# G826K.net
KiCad netlist of a schematic drawn in EAGLE
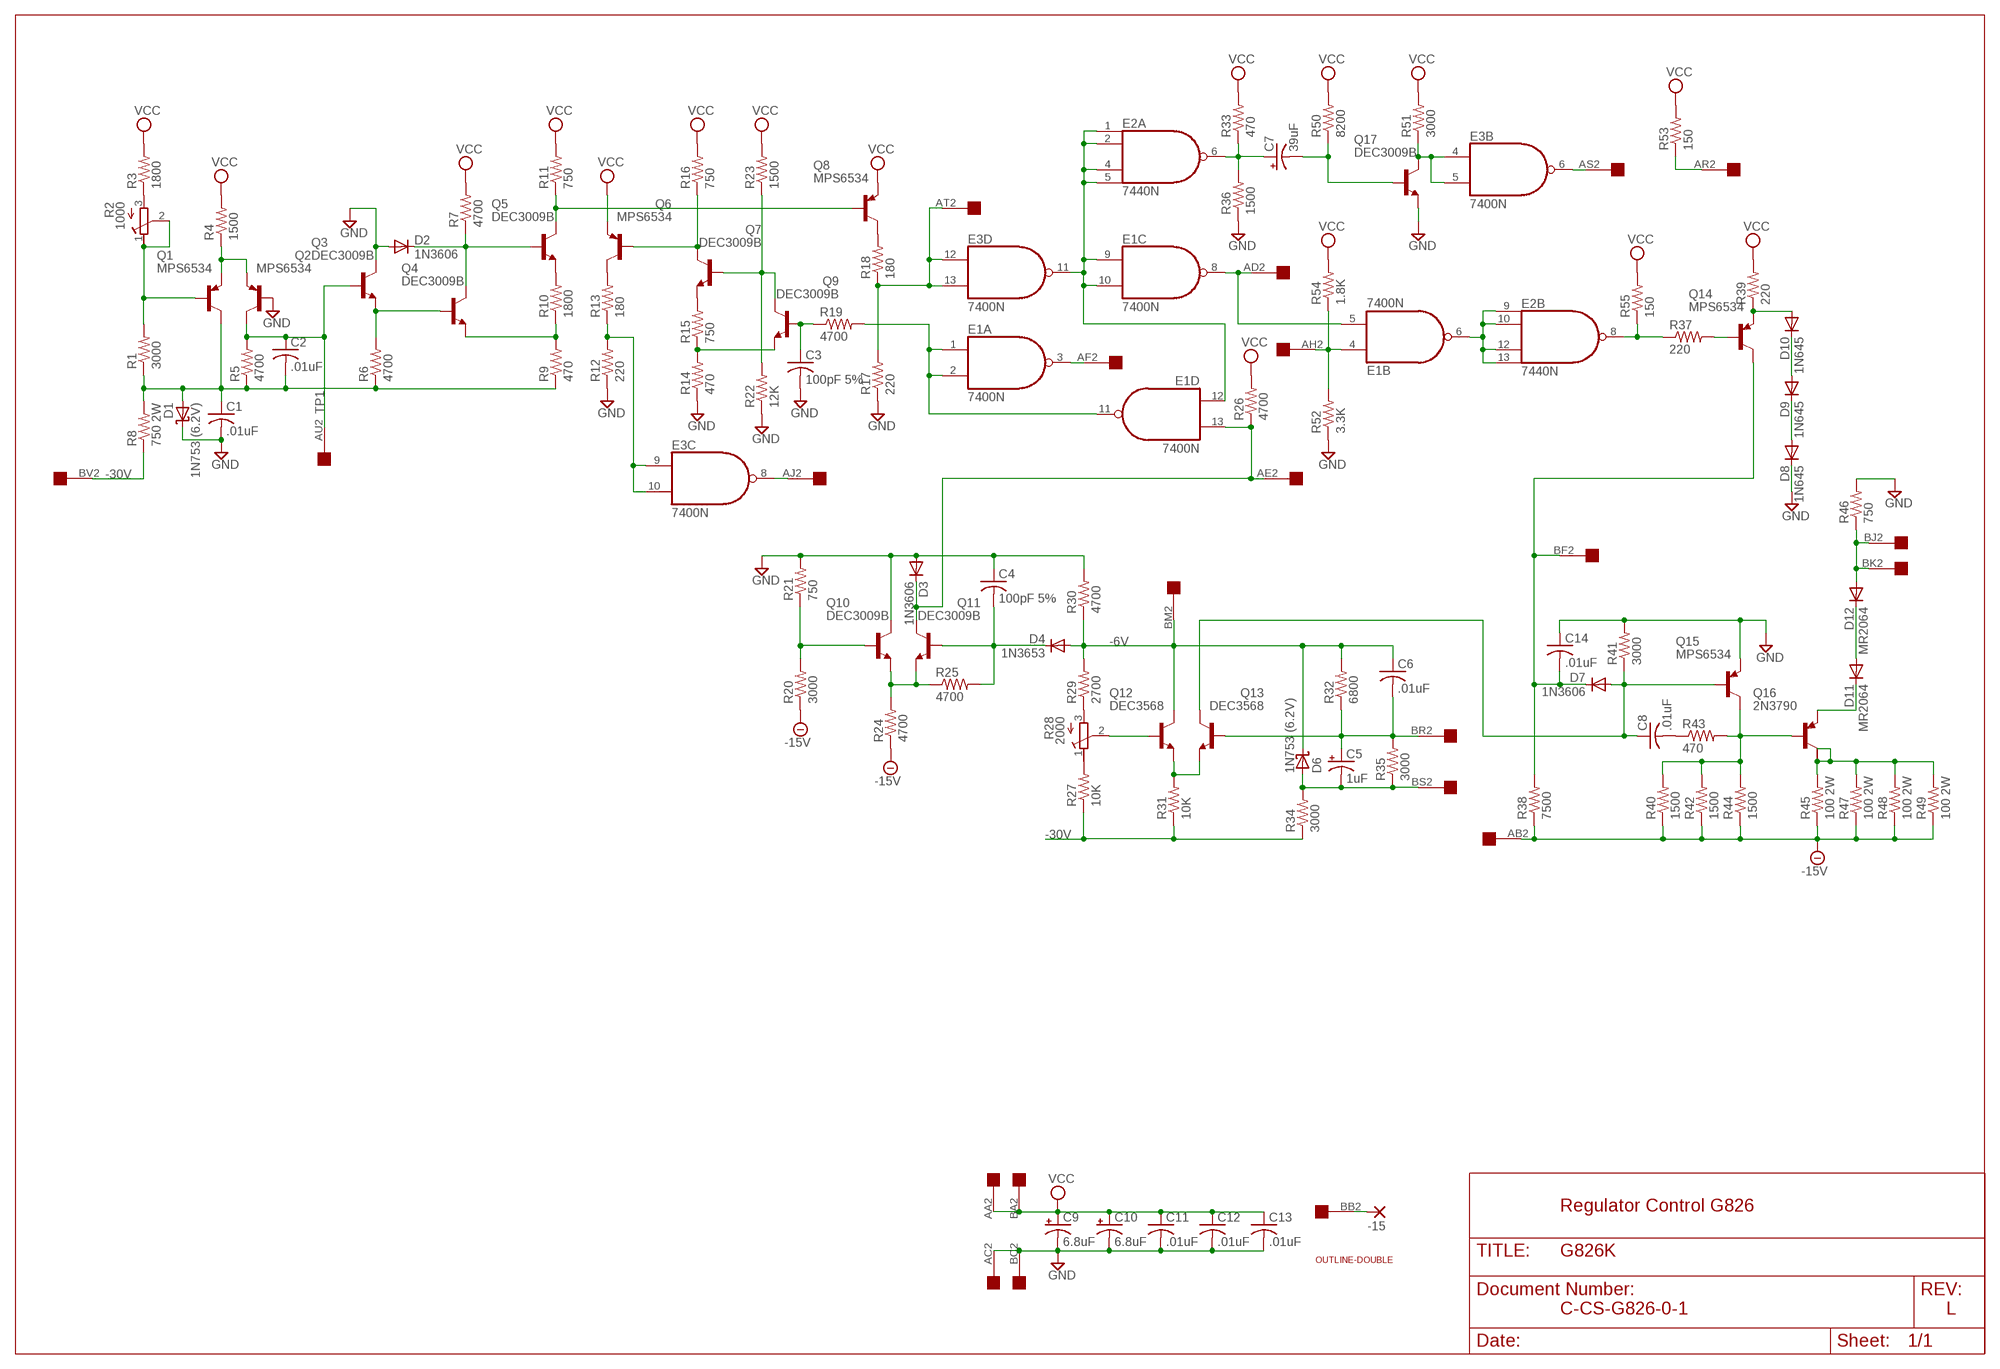
[diagram p0: schematic, sheet 1]

(export (version "E")
  (design (tool "Eeschema 10.0.6"))
  (components
    (comp (ref "-15")
      (value "1,6/0,8")
      (footprint "eagle-import:1,6_0,8")
      (libsource (lib "eagle-import") (part "1,6/0,8"))
    )
    (comp (ref "C1")
      (value ".01uF")
      (footprint "eagle-import:C050-025X075")
      (libsource (lib "eagle-import") (part "C-US050-025X075"))
    )
    (comp (ref "C2")
      (value ".01uF")
      (footprint "eagle-import:C050-025X075")
      (libsource (lib "eagle-import") (part "C-US050-025X075"))
    )
    (comp (ref "C3")
      (value "100pF 5%")
      (footprint "eagle-import:C050-025X075")
      (libsource (lib "eagle-import") (part "C-US050-025X075"))
    )
    (comp (ref "C4")
      (value "100pF 5%")
      (footprint "eagle-import:C050-025X075")
      (libsource (lib "eagle-import") (part "C-US050-025X075"))
    )
    (comp (ref "C5")
      (value "1uF")
      (footprint "eagle-import:E15-5")
      (libsource (lib "eagle-import") (part "CPOL-USE15-5AXIAL"))
    )
    (comp (ref "C6")
      (value ".01uF")
      (footprint "eagle-import:C050-025X075")
      (libsource (lib "eagle-import") (part "C-US050-025X075"))
    )
    (comp (ref "C7")
      (value "39uF")
      (footprint "eagle-import:E22-6")
      (libsource (lib "eagle-import") (part "CPOL-USE22-6AXIAL"))
    )
    (comp (ref "C8")
      (value ".01uF")
      (footprint "eagle-import:C050-025X075")
      (libsource (lib "eagle-import") (part "C-US050-025X075"))
    )
    (comp (ref "C9")
      (value "6.8uF")
      (footprint "eagle-import:E12-8")
      (libsource (lib "eagle-import") (part "CPOL-USE20-8AXIAL"))
    )
    (comp (ref "C10")
      (value "6.8uF")
      (footprint "eagle-import:E12-8")
      (libsource (lib "eagle-import") (part "CPOL-USE20-8AXIAL"))
    )
    (comp (ref "C11")
      (value ".01uF")
      (footprint "eagle-import:C050-025X075")
      (libsource (lib "eagle-import") (part "C-US050-025X075"))
    )
    (comp (ref "C12")
      (value ".01uF")
      (footprint "eagle-import:C050-025X075")
      (libsource (lib "eagle-import") (part "C-US050-025X075"))
    )
    (comp (ref "C13")
      (value ".01uF")
      (footprint "eagle-import:C050-025X075")
      (libsource (lib "eagle-import") (part "C-US050-025X075"))
    )
    (comp (ref "C14")
      (value ".01uF")
      (footprint "eagle-import:C050-025X075")
      (libsource (lib "eagle-import") (part "C-US050-025X075"))
    )
    (comp (ref "D1")
      (value "1N753 (6.2V)")
      (footprint "eagle-import:DO35-10")
      (libsource (lib "eagle-import") (part "BAT42"))
    )
    (comp (ref "D2")
      (value "1N3606")
      (footprint "eagle-import:DO35-10")
      (libsource (lib "eagle-import") (part "1N4148"))
    )
    (comp (ref "D3")
      (value "1N3606")
      (footprint "eagle-import:DO35-10")
      (libsource (lib "eagle-import") (part "1N4148"))
    )
    (comp (ref "D4")
      (value "1N3653")
      (footprint "eagle-import:DO35-10")
      (libsource (lib "eagle-import") (part "1N4148"))
    )
    (comp (ref "D6")
      (value "1N753 (6.2V)")
      (footprint "eagle-import:DO35-10")
      (libsource (lib "eagle-import") (part "BAT42"))
    )
    (comp (ref "D7")
      (value "1N3606")
      (footprint "eagle-import:DO35-10")
      (libsource (lib "eagle-import") (part "1N4148"))
    )
    (comp (ref "D8")
      (value "1N645")
      (footprint "eagle-import:DO35-10")
      (libsource (lib "eagle-import") (part "1N4148"))
    )
    (comp (ref "D9")
      (value "1N645")
      (footprint "eagle-import:DO35-10")
      (libsource (lib "eagle-import") (part "1N4148"))
    )
    (comp (ref "D10")
      (value "1N645")
      (footprint "eagle-import:DO35-10")
      (libsource (lib "eagle-import") (part "1N4148"))
    )
    (comp (ref "D11")
      (value "MR2064")
      (footprint "eagle-import:DO41-10")
      (libsource (lib "eagle-import") (part "1N4004"))
    )
    (comp (ref "D12")
      (value "MR2064")
      (footprint "eagle-import:DO41-10")
      (libsource (lib "eagle-import") (part "1N4004"))
    )
    (comp (ref "E1")
      (value "7400N")
      (footprint "eagle-import:DIL14")
      (libsource (lib "eagle-import") (part "7400N"))
    )
    (comp (ref "E2")
      (value "7440N")
      (footprint "eagle-import:DIL14")
      (libsource (lib "eagle-import") (part "7420NS"))
    )
    (comp (ref "E3")
      (value "7400N")
      (footprint "eagle-import:DIL14")
      (libsource (lib "eagle-import") (part "7400N"))
    )
    (comp (ref "Q1")
      (value "MPS6534")
      (footprint "eagle-import:TO39")
      (libsource (lib "eagle-import") (part "2N2904"))
    )
    (comp (ref "Q2")
      (value "MPS6534")
      (footprint "eagle-import:TO39")
      (libsource (lib "eagle-import") (part "2N2904"))
    )
    (comp (ref "Q3")
      (value "DEC3009B")
      (footprint "eagle-import:TO5")
      (libsource (lib "eagle-import") (part "2N2219"))
    )
    (comp (ref "Q4")
      (value "DEC3009B")
      (footprint "eagle-import:TO5")
      (libsource (lib "eagle-import") (part "2N2219"))
    )
    (comp (ref "Q5")
      (value "DEC3009B")
      (footprint "eagle-import:TO5")
      (libsource (lib "eagle-import") (part "2N2219"))
    )
    (comp (ref "Q6")
      (value "MPS6534")
      (footprint "eagle-import:TO39")
      (libsource (lib "eagle-import") (part "2N2904"))
    )
    (comp (ref "Q7")
      (value "DEC3009B")
      (footprint "eagle-import:TO5")
      (libsource (lib "eagle-import") (part "2N2219"))
    )
    (comp (ref "Q8")
      (value "MPS6534")
      (footprint "eagle-import:TO39")
      (libsource (lib "eagle-import") (part "2N2904"))
    )
    (comp (ref "Q9")
      (value "DEC3009B")
      (footprint "eagle-import:TO5")
      (libsource (lib "eagle-import") (part "2N2219"))
    )
    (comp (ref "Q10")
      (value "DEC3009B")
      (footprint "eagle-import:TO5")
      (libsource (lib "eagle-import") (part "2N2219"))
    )
    (comp (ref "Q11")
      (value "DEC3009B")
      (footprint "eagle-import:TO5")
      (libsource (lib "eagle-import") (part "2N2219"))
    )
    (comp (ref "Q12")
      (value "DEC3568")
      (footprint "eagle-import:TO5")
      (libsource (lib "eagle-import") (part "2N2219"))
    )
    (comp (ref "Q13")
      (value "DEC3568")
      (footprint "eagle-import:TO5")
      (libsource (lib "eagle-import") (part "2N2219"))
    )
    (comp (ref "Q14")
      (value "MPS6534")
      (footprint "eagle-import:TO39")
      (libsource (lib "eagle-import") (part "2N2904"))
    )
    (comp (ref "Q15")
      (value "MPS6534")
      (footprint "eagle-import:TO39")
      (libsource (lib "eagle-import") (part "2N2904"))
    )
    (comp (ref "Q16")
      (value "2N3790")
      (footprint "eagle-import:TO3")
      (libsource (lib "eagle-import") (part "2N4902"))
    )
    (comp (ref "Q17")
      (value "DEC3009B")
      (footprint "eagle-import:TO5")
      (libsource (lib "eagle-import") (part "2N2219"))
    )
    (comp (ref "R1")
      (value "3000")
      (footprint "eagle-import:0207_10")
      (libsource (lib "eagle-import") (part "R-US_0207/10"))
    )
    (comp (ref "R2")
      (value "1000")
      (footprint "eagle-import:3006Y")
      (libsource (lib "eagle-import") (part "275P"))
    )
    (comp (ref "R3")
      (value "1800")
      (footprint "eagle-import:0207_10")
      (libsource (lib "eagle-import") (part "R-US_0207/10"))
    )
    (comp (ref "R4")
      (value "1500")
      (footprint "eagle-import:0207_10")
      (libsource (lib "eagle-import") (part "R-US_0207/10"))
    )
    (comp (ref "R5")
      (value "4700")
      (footprint "eagle-import:0207_10")
      (libsource (lib "eagle-import") (part "R-US_0207/10"))
    )
    (comp (ref "R6")
      (value "4700")
      (footprint "eagle-import:0207_10")
      (libsource (lib "eagle-import") (part "R-US_0207/10"))
    )
    (comp (ref "R7")
      (value "4700")
      (footprint "eagle-import:0207_10")
      (libsource (lib "eagle-import") (part "R-US_0207/10"))
    )
    (comp (ref "R8")
      (value "750 2W")
      (footprint "eagle-import:0818_25")
      (libsource (lib "eagle-import") (part "R-US_0818/25"))
    )
    (comp (ref "R9")
      (value "470")
      (footprint "eagle-import:0207_10")
      (libsource (lib "eagle-import") (part "R-US_0207/10"))
    )
    (comp (ref "R10")
      (value "1800")
      (footprint "eagle-import:0207_10")
      (libsource (lib "eagle-import") (part "R-US_0207/10"))
    )
    (comp (ref "R11")
      (value "750")
      (footprint "eagle-import:0207_10")
      (libsource (lib "eagle-import") (part "R-US_0207/10"))
    )
    (comp (ref "R12")
      (value "220")
      (footprint "eagle-import:0207_10")
      (libsource (lib "eagle-import") (part "R-US_0207/10"))
    )
    (comp (ref "R13")
      (value "180")
      (footprint "eagle-import:0207_10")
      (libsource (lib "eagle-import") (part "R-US_0207/10"))
    )
    (comp (ref "R14")
      (value "470")
      (footprint "eagle-import:0207_10")
      (libsource (lib "eagle-import") (part "R-US_0207/10"))
    )
    (comp (ref "R15")
      (value "750")
      (footprint "eagle-import:0207_10")
      (libsource (lib "eagle-import") (part "R-US_0207/10"))
    )
    (comp (ref "R16")
      (value "750")
      (footprint "eagle-import:0207_10")
      (libsource (lib "eagle-import") (part "R-US_0207/10"))
    )
    (comp (ref "R17")
      (value "220")
      (footprint "eagle-import:0207_10")
      (libsource (lib "eagle-import") (part "R-US_0207/10"))
    )
    (comp (ref "R18")
      (value "180")
      (footprint "eagle-import:0207_10")
      (libsource (lib "eagle-import") (part "R-US_0207/10"))
    )
    (comp (ref "R19")
      (value "4700")
      (footprint "eagle-import:0207_10")
      (libsource (lib "eagle-import") (part "R-US_0207/10"))
    )
    (comp (ref "R20")
      (value "3000")
      (footprint "eagle-import:0207_10")
      (libsource (lib "eagle-import") (part "R-US_0207/10"))
    )
    (comp (ref "R21")
      (value "750")
      (footprint "eagle-import:0207_10")
      (libsource (lib "eagle-import") (part "R-US_0207/10"))
    )
    (comp (ref "R22")
      (value "12K")
      (footprint "eagle-import:0207_10")
      (libsource (lib "eagle-import") (part "R-US_0207/10"))
    )
    (comp (ref "R23")
      (value "1500")
      (footprint "eagle-import:0207_10")
      (libsource (lib "eagle-import") (part "R-US_0207/10"))
    )
    (comp (ref "R24")
      (value "4700")
      (footprint "eagle-import:0207_10")
      (libsource (lib "eagle-import") (part "R-US_0207/10"))
    )
    (comp (ref "R25")
      (value "4700")
      (footprint "eagle-import:0207_10")
      (libsource (lib "eagle-import") (part "R-US_0207/10"))
    )
    (comp (ref "R26")
      (value "4700")
      (footprint "eagle-import:0207_10")
      (libsource (lib "eagle-import") (part "R-US_0207/10"))
    )
    (comp (ref "R27")
      (value "10K")
      (footprint "eagle-import:0207_10")
      (libsource (lib "eagle-import") (part "R-US_0207/10"))
    )
    (comp (ref "R28")
      (value "2000")
      (footprint "eagle-import:3006Y")
      (libsource (lib "eagle-import") (part "275P"))
    )
    (comp (ref "R29")
      (value "2700")
      (footprint "eagle-import:0207_10")
      (libsource (lib "eagle-import") (part "R-US_0207/10"))
    )
    (comp (ref "R30")
      (value "4700")
      (footprint "eagle-import:0207_10")
      (libsource (lib "eagle-import") (part "R-US_0207/10"))
    )
    (comp (ref "R31")
      (value "10K")
      (footprint "eagle-import:0207_10")
      (libsource (lib "eagle-import") (part "R-US_0207/10"))
    )
    (comp (ref "R32")
      (value "6800")
      (footprint "eagle-import:0207_10")
      (libsource (lib "eagle-import") (part "R-US_0207/10"))
    )
    (comp (ref "R33")
      (value "470")
      (footprint "eagle-import:0207_10")
      (libsource (lib "eagle-import") (part "R-US_0207/10"))
    )
    (comp (ref "R34")
      (value "3000")
      (footprint "eagle-import:0207_10")
      (libsource (lib "eagle-import") (part "R-US_0207/10"))
    )
    (comp (ref "R35")
      (value "3000")
      (footprint "eagle-import:0207_10")
      (libsource (lib "eagle-import") (part "R-US_0207/10"))
    )
    (comp (ref "R36")
      (value "1500")
      (footprint "eagle-import:0207_10")
      (libsource (lib "eagle-import") (part "R-US_0207/10"))
    )
    (comp (ref "R37")
      (value "220")
      (footprint "eagle-import:0207_10")
      (libsource (lib "eagle-import") (part "R-US_0207/10"))
    )
    (comp (ref "R38")
      (value "7500")
      (footprint "eagle-import:0207_10")
      (libsource (lib "eagle-import") (part "R-US_0207/10"))
    )
    (comp (ref "R39")
      (value "220")
      (footprint "eagle-import:0207_10")
      (libsource (lib "eagle-import") (part "R-US_0207/10"))
    )
    (comp (ref "R40")
      (value "1500")
      (footprint "eagle-import:0207_10")
      (libsource (lib "eagle-import") (part "R-US_0207/10"))
    )
    (comp (ref "R41")
      (value "3000")
      (footprint "eagle-import:0207_10")
      (libsource (lib "eagle-import") (part "R-US_0207/10"))
    )
    (comp (ref "R42")
      (value "1500")
      (footprint "eagle-import:0207_10")
      (libsource (lib "eagle-import") (part "R-US_0207/10"))
    )
    (comp (ref "R43")
      (value "470")
      (footprint "eagle-import:0207_10")
      (libsource (lib "eagle-import") (part "R-US_0207/10"))
    )
    (comp (ref "R44")
      (value "1500")
      (footprint "eagle-import:0207_10")
      (libsource (lib "eagle-import") (part "R-US_0207/10"))
    )
    (comp (ref "R45")
      (value "100 2W")
      (footprint "eagle-import:0818_25")
      (libsource (lib "eagle-import") (part "R-US_0818/25"))
    )
    (comp (ref "R46")
      (value "750")
      (footprint "eagle-import:0207_10")
      (libsource (lib "eagle-import") (part "R-US_0207/10"))
    )
    (comp (ref "R47")
      (value "100 2W")
      (footprint "eagle-import:0818_25")
      (libsource (lib "eagle-import") (part "R-US_0818/25"))
    )
    (comp (ref "R48")
      (value "100 2W")
      (footprint "eagle-import:0818_25")
      (libsource (lib "eagle-import") (part "R-US_0818/25"))
    )
    (comp (ref "R49")
      (value "100 2W")
      (footprint "eagle-import:0818_25")
      (libsource (lib "eagle-import") (part "R-US_0818/25"))
    )
    (comp (ref "R50")
      (value "8200")
      (footprint "eagle-import:0207_10")
      (libsource (lib "eagle-import") (part "R-US_0207/10"))
    )
    (comp (ref "R51")
      (value "3000")
      (footprint "eagle-import:0207_10")
      (libsource (lib "eagle-import") (part "R-US_0207/10"))
    )
    (comp (ref "R52")
      (value "3.3K")
      (footprint "eagle-import:0207_10")
      (libsource (lib "eagle-import") (part "R-US_0207/10"))
    )
    (comp (ref "R53")
      (value "150")
      (footprint "eagle-import:0207_10")
      (libsource (lib "eagle-import") (part "R-US_0207/10"))
    )
    (comp (ref "R54")
      (value "1.8K")
      (footprint "eagle-import:0207_10")
      (libsource (lib "eagle-import") (part "R-US_0207/10"))
    )
    (comp (ref "R55")
      (value "150")
      (footprint "eagle-import:0207_10")
      (libsource (lib "eagle-import") (part "R-US_0207/10"))
    )
    (comp (ref "U$1")
      (value "DOUBLE")
      (footprint "eagle-import:EDGE-CON4")
      (libsource (lib "eagle-import") (part "DOUBLE"))
    )
    (comp (ref "U$2")
      (value "OUTLINE-DOUBLE")
      (footprint "eagle-import:DOUBLE")
      (libsource (lib "eagle-import") (part "OUTLINE-DOUBLE"))
    )
  )
  (nets
    (net (code "1") (name "-15V") (class "Default")
      (node (ref "R20") (pin "1") (pinfunction "1_1") (pintype "passive"))
      (node (ref "R24") (pin "1") (pinfunction "1_1") (pintype "passive"))
      (node (ref "R38") (pin "1") (pinfunction "1_1") (pintype "passive"))
      (node (ref "R40") (pin "1") (pinfunction "1_1") (pintype "passive"))
      (node (ref "R42") (pin "1") (pinfunction "1_1") (pintype "passive"))
      (node (ref "R44") (pin "1") (pinfunction "1_1") (pintype "passive"))
      (node (ref "R45") (pin "1") (pinfunction "1_1") (pintype "passive"))
      (node (ref "R47") (pin "1") (pinfunction "1_1") (pintype "passive"))
      (node (ref "R48") (pin "1") (pinfunction "1_1") (pintype "passive"))
      (node (ref "R49") (pin "1") (pinfunction "1_1") (pintype "passive"))
      (node (ref "U$1") (pin "AB2") (pinfunction "1_AB2") (pintype "bidirectional"))
    )
    (net (code "2") (name "/-6V") (class "Default")
      (node (ref "C6") (pin "1") (pinfunction "1_1") (pintype "passive"))
      (node (ref "D4") (pin "A") (pinfunction "A_A") (pintype "passive"))
      (node (ref "D6") (pin "C") (pinfunction "C_C") (pintype "passive"))
      (node (ref "Q12") (pin "3") (pinfunction "C_3") (pintype "passive"))
      (node (ref "R29") (pin "2") (pinfunction "2_2") (pintype "passive"))
      (node (ref "R30") (pin "1") (pinfunction "1_1") (pintype "passive"))
      (node (ref "R32") (pin "2") (pinfunction "2_2") (pintype "passive"))
      (node (ref "U$1") (pin "BM2") (pinfunction "1_BM2") (pintype "bidirectional"))
    )
    (net (code "3") (name "/-30V") (class "Default")
      (node (ref "R27") (pin "1") (pinfunction "1_1") (pintype "passive"))
      (node (ref "R31") (pin "1") (pinfunction "1_1") (pintype "passive"))
      (node (ref "R34") (pin "1") (pinfunction "1_1") (pintype "passive"))
      (node (ref "R8") (pin "1") (pinfunction "1_1") (pintype "passive"))
      (node (ref "U$1") (pin "BV2") (pinfunction "1_BV2") (pintype "bidirectional"))
    )
    (net (code "4") (name "/TP1") (class "Default")
      (node (ref "C2") (pin "1") (pinfunction "1_1") (pintype "passive"))
      (node (ref "Q2") (pin "3") (pinfunction "C_3") (pintype "passive"))
      (node (ref "Q3") (pin "2") (pinfunction "B_2") (pintype "passive"))
      (node (ref "R5") (pin "2") (pinfunction "2_2") (pintype "passive"))
      (node (ref "U$1") (pin "AU2") (pinfunction "1_AU2") (pintype "bidirectional"))
    )
    (net (code "5") (name "GND") (class "Default")
      (node (ref "C1") (pin "2") (pinfunction "2_2") (pintype "passive"))
      (node (ref "C10") (pin "-") (pinfunction "-_-") (pintype "passive"))
      (node (ref "C11") (pin "2") (pinfunction "2_2") (pintype "passive"))
      (node (ref "C12") (pin "2") (pinfunction "2_2") (pintype "passive"))
      (node (ref "C13") (pin "2") (pinfunction "2_2") (pintype "passive"))
      (node (ref "C14") (pin "1") (pinfunction "1_1") (pintype "passive"))
      (node (ref "C3") (pin "2") (pinfunction "2_2") (pintype "passive"))
      (node (ref "C4") (pin "1") (pinfunction "1_1") (pintype "passive"))
      (node (ref "C9") (pin "-") (pinfunction "-_-") (pintype "passive"))
      (node (ref "D1") (pin "C") (pinfunction "C_C") (pintype "passive"))
      (node (ref "D2") (pin "A") (pinfunction "A_A") (pintype "passive"))
      (node (ref "D3") (pin "A") (pinfunction "A_A") (pintype "passive"))
      (node (ref "D8") (pin "C") (pinfunction "C_C") (pintype "passive"))
      (node (ref "Q10") (pin "3") (pinfunction "C_3") (pintype "passive"))
      (node (ref "Q15") (pin "1") (pinfunction "E_1") (pintype "passive"))
      (node (ref "Q17") (pin "1") (pinfunction "E_1") (pintype "passive"))
      (node (ref "Q2") (pin "2") (pinfunction "B_2") (pintype "passive"))
      (node (ref "Q3") (pin "3") (pinfunction "C_3") (pintype "passive"))
      (node (ref "R12") (pin "1") (pinfunction "1_1") (pintype "passive"))
      (node (ref "R14") (pin "1") (pinfunction "1_1") (pintype "passive"))
      (node (ref "R17") (pin "1") (pinfunction "1_1") (pintype "passive"))
      (node (ref "R21") (pin "2") (pinfunction "2_2") (pintype "passive"))
      (node (ref "R22") (pin "1") (pinfunction "1_1") (pintype "passive"))
      (node (ref "R30") (pin "2") (pinfunction "2_2") (pintype "passive"))
      (node (ref "R36") (pin "1") (pinfunction "1_1") (pintype "passive"))
      (node (ref "R41") (pin "2") (pinfunction "2_2") (pintype "passive"))
      (node (ref "R46") (pin "2") (pinfunction "2_2") (pintype "passive"))
      (node (ref "R52") (pin "1") (pinfunction "1_1") (pintype "passive"))
      (node (ref "U$1") (pin "AC2") (pinfunction "1_AC2") (pintype "bidirectional"))
      (node (ref "U$1") (pin "BC2") (pinfunction "1_BC2") (pintype "bidirectional"))
    )
    (net (code "6") (name "Net-(-15-P)") (class "Default")
      (node (ref "-15") (pin "1") (pinfunction "P_1") (pintype "passive"))
      (node (ref "U$1") (pin "BB2") (pinfunction "1_BB2") (pintype "bidirectional"))
    )
    (net (code "7") (name "Net-(C8-Pad2)") (class "Default")
      (node (ref "C8") (pin "2") (pinfunction "2_2") (pintype "passive"))
      (node (ref "R43") (pin "1") (pinfunction "1_1") (pintype "passive"))
    )
    (net (code "8") (name "Net-(D8-PadA)") (class "Default")
      (node (ref "D8") (pin "A") (pinfunction "A_A") (pintype "passive"))
      (node (ref "D9") (pin "C") (pinfunction "C_C") (pintype "passive"))
    )
    (net (code "9") (name "Net-(D10-PadC)") (class "Default")
      (node (ref "D10") (pin "C") (pinfunction "C_C") (pintype "passive"))
      (node (ref "D9") (pin "A") (pinfunction "A_A") (pintype "passive"))
    )
    (net (code "10") (name "Net-(D11-PadA)") (class "Default")
      (node (ref "D11") (pin "A") (pinfunction "A_A") (pintype "passive"))
      (node (ref "D12") (pin "C") (pinfunction "C_C") (pintype "passive"))
    )
    (net (code "11") (name "Net-(D11-PadC)") (class "Default")
      (node (ref "D11") (pin "C") (pinfunction "C_C") (pintype "passive"))
      (node (ref "Q16") (pin "E") (pinfunction "E_E") (pintype "passive"))
    )
    (net (code "12") (name "Net-(E1A-I0)") (class "Default")
      (node (ref "E1") (pin "1") (pinfunction "I0_1") (pintype "input"))
      (node (ref "E1") (pin "11") (pinfunction "O_11") (pintype "output"))
      (node (ref "E1") (pin "2") (pinfunction "I1_2") (pintype "input"))
      (node (ref "R19") (pin "2") (pinfunction "2_2") (pintype "passive"))
    )
    (net (code "13") (name "Net-(E1A-O)") (class "Default")
      (node (ref "E1") (pin "3") (pinfunction "O_3") (pintype "output"))
      (node (ref "U$1") (pin "AF2") (pinfunction "1_AF2") (pintype "bidirectional"))
    )
    (net (code "14") (name "Net-(E1B-I0)") (class "Default")
      (node (ref "E1") (pin "4") (pinfunction "I0_4") (pintype "input"))
      (node (ref "R52") (pin "2") (pinfunction "2_2") (pintype "passive"))
      (node (ref "R54") (pin "1") (pinfunction "1_1") (pintype "passive"))
      (node (ref "U$1") (pin "AH2") (pinfunction "1_AH2") (pintype "bidirectional"))
    )
    (net (code "15") (name "Net-(E1B-I1)") (class "Default")
      (node (ref "E1") (pin "5") (pinfunction "I1_5") (pintype "input"))
      (node (ref "E1") (pin "8") (pinfunction "O_8") (pintype "output"))
      (node (ref "U$1") (pin "AD2") (pinfunction "1_AD2") (pintype "bidirectional"))
    )
    (net (code "16") (name "Net-(E1B-O)") (class "Default")
      (node (ref "E1") (pin "6") (pinfunction "O_6") (pintype "output"))
      (node (ref "E2") (pin "10") (pinfunction "I1_10") (pintype "input"))
      (node (ref "E2") (pin "12") (pinfunction "I2_12") (pintype "input"))
      (node (ref "E2") (pin "13") (pinfunction "I3_13") (pintype "input"))
      (node (ref "E2") (pin "9") (pinfunction "I0_9") (pintype "input"))
    )
    (net (code "17") (name "Net-(E1C-I0)") (class "Default")
      (node (ref "E1") (pin "10") (pinfunction "I1_10") (pintype "input"))
      (node (ref "E1") (pin "12") (pinfunction "I0_12") (pintype "input"))
      (node (ref "E1") (pin "9") (pinfunction "I0_9") (pintype "input"))
      (node (ref "E2") (pin "1") (pinfunction "I0_1") (pintype "input"))
      (node (ref "E2") (pin "2") (pinfunction "I1_2") (pintype "input"))
      (node (ref "E2") (pin "4") (pinfunction "I2_4") (pintype "input"))
      (node (ref "E2") (pin "5") (pinfunction "I3_5") (pintype "input"))
      (node (ref "E3") (pin "11") (pinfunction "O_11") (pintype "output"))
    )
    (net (code "18") (name "Net-(E1D-I1)") (class "Default")
      (node (ref "D3") (pin "C") (pinfunction "C_C") (pintype "passive"))
      (node (ref "E1") (pin "13") (pinfunction "I1_13") (pintype "input"))
      (node (ref "Q11") (pin "3") (pinfunction "C_3") (pintype "passive"))
      (node (ref "R26") (pin "1") (pinfunction "1_1") (pintype "passive"))
      (node (ref "U$1") (pin "AE2") (pinfunction "1_AE2") (pintype "bidirectional"))
    )
    (net (code "19") (name "Net-(E2A-O)") (class "Default")
      (node (ref "C7") (pin "+") (pinfunction "+_+") (pintype "passive"))
      (node (ref "E2") (pin "6") (pinfunction "O_6") (pintype "output"))
      (node (ref "R33") (pin "1") (pinfunction "1_1") (pintype "passive"))
      (node (ref "R36") (pin "2") (pinfunction "2_2") (pintype "passive"))
    )
    (net (code "20") (name "Net-(E2B-O)") (class "Default")
      (node (ref "E2") (pin "8") (pinfunction "O_8") (pintype "output"))
      (node (ref "R37") (pin "1") (pinfunction "1_1") (pintype "passive"))
      (node (ref "R55") (pin "1") (pinfunction "1_1") (pintype "passive"))
    )
    (net (code "21") (name "Net-(E3B-I0)") (class "Default")
      (node (ref "E3") (pin "4") (pinfunction "I0_4") (pintype "input"))
      (node (ref "E3") (pin "5") (pinfunction "I1_5") (pintype "input"))
      (node (ref "Q17") (pin "3") (pinfunction "C_3") (pintype "passive"))
      (node (ref "R51") (pin "1") (pinfunction "1_1") (pintype "passive"))
    )
    (net (code "22") (name "Net-(E3B-O)") (class "Default")
      (node (ref "E3") (pin "6") (pinfunction "O_6") (pintype "output"))
      (node (ref "U$1") (pin "AS2") (pinfunction "1_AS2") (pintype "bidirectional"))
    )
    (net (code "23") (name "Net-(E3C-I0)") (class "Default")
      (node (ref "E3") (pin "10") (pinfunction "I1_10") (pintype "input"))
      (node (ref "E3") (pin "9") (pinfunction "I0_9") (pintype "input"))
      (node (ref "R12") (pin "2") (pinfunction "2_2") (pintype "passive"))
      (node (ref "R13") (pin "1") (pinfunction "1_1") (pintype "passive"))
    )
    (net (code "24") (name "Net-(E3C-O)") (class "Default")
      (node (ref "E3") (pin "8") (pinfunction "O_8") (pintype "output"))
      (node (ref "U$1") (pin "AJ2") (pinfunction "1_AJ2") (pintype "bidirectional"))
    )
    (net (code "25") (name "Net-(E3D-I0)") (class "Default")
      (node (ref "E3") (pin "12") (pinfunction "I0_12") (pintype "input"))
      (node (ref "E3") (pin "13") (pinfunction "I1_13") (pintype "input"))
      (node (ref "R17") (pin "2") (pinfunction "2_2") (pintype "passive"))
      (node (ref "R18") (pin "1") (pinfunction "1_1") (pintype "passive"))
      (node (ref "U$1") (pin "AT2") (pinfunction "1_AT2") (pintype "bidirectional"))
    )
    (net (code "26") (name "Net-(Q1-B)") (class "Default")
      (node (ref "Q1") (pin "2") (pinfunction "B_2") (pintype "passive"))
      (node (ref "R1") (pin "2") (pinfunction "2_2") (pintype "passive"))
      (node (ref "R2") (pin "1") (pinfunction "A_1") (pintype "passive"))
      (node (ref "R2") (pin "2") (pinfunction "S_2") (pintype "passive"))
    )
    (net (code "27") (name "Net-(Q1-C)") (class "Default")
      (node (ref "C1") (pin "1") (pinfunction "1_1") (pintype "passive"))
      (node (ref "C2") (pin "2") (pinfunction "2_2") (pintype "passive"))
      (node (ref "D1") (pin "A") (pinfunction "A_A") (pintype "passive"))
      (node (ref "Q1") (pin "3") (pinfunction "C_3") (pintype "passive"))
      (node (ref "R1") (pin "1") (pinfunction "1_1") (pintype "passive"))
      (node (ref "R5") (pin "1") (pinfunction "1_1") (pintype "passive"))
      (node (ref "R6") (pin "1") (pinfunction "1_1") (pintype "passive"))
      (node (ref "R8") (pin "2") (pinfunction "2_2") (pintype "passive"))
      (node (ref "R9") (pin "1") (pinfunction "1_1") (pintype "passive"))
    )
    (net (code "28") (name "Net-(Q1-E)") (class "Default")
      (node (ref "Q1") (pin "1") (pinfunction "E_1") (pintype "passive"))
      (node (ref "Q2") (pin "1") (pinfunction "E_1") (pintype "passive"))
      (node (ref "R4") (pin "1") (pinfunction "1_1") (pintype "passive"))
    )
    (net (code "29") (name "Net-(Q3-E)") (class "Default")
      (node (ref "Q3") (pin "1") (pinfunction "E_1") (pintype "passive"))
      (node (ref "Q4") (pin "2") (pinfunction "B_2") (pintype "passive"))
      (node (ref "R6") (pin "2") (pinfunction "2_2") (pintype "passive"))
    )
    (net (code "30") (name "Net-(Q4-C)") (class "Default")
      (node (ref "D2") (pin "C") (pinfunction "C_C") (pintype "passive"))
      (node (ref "Q4") (pin "3") (pinfunction "C_3") (pintype "passive"))
      (node (ref "Q5") (pin "2") (pinfunction "B_2") (pintype "passive"))
      (node (ref "R7") (pin "1") (pinfunction "1_1") (pintype "passive"))
    )
    (net (code "31") (name "Net-(Q4-E)") (class "Default")
      (node (ref "Q4") (pin "1") (pinfunction "E_1") (pintype "passive"))
      (node (ref "R10") (pin "1") (pinfunction "1_1") (pintype "passive"))
      (node (ref "R9") (pin "2") (pinfunction "2_2") (pintype "passive"))
    )
    (net (code "32") (name "Net-(Q5-C)") (class "Default")
      (node (ref "Q5") (pin "3") (pinfunction "C_3") (pintype "passive"))
      (node (ref "Q8") (pin "2") (pinfunction "B_2") (pintype "passive"))
      (node (ref "R11") (pin "1") (pinfunction "1_1") (pintype "passive"))
    )
    (net (code "33") (name "Net-(Q5-E)") (class "Default")
      (node (ref "Q5") (pin "1") (pinfunction "E_1") (pintype "passive"))
      (node (ref "R10") (pin "2") (pinfunction "2_2") (pintype "passive"))
    )
    (net (code "34") (name "Net-(Q6-B)") (class "Default")
      (node (ref "Q6") (pin "2") (pinfunction "B_2") (pintype "passive"))
      (node (ref "Q7") (pin "3") (pinfunction "C_3") (pintype "passive"))
      (node (ref "R16") (pin "1") (pinfunction "1_1") (pintype "passive"))
    )
    (net (code "35") (name "Net-(Q6-C)") (class "Default")
      (node (ref "Q6") (pin "3") (pinfunction "C_3") (pintype "passive"))
      (node (ref "R13") (pin "2") (pinfunction "2_2") (pintype "passive"))
    )
    (net (code "36") (name "Net-(Q7-B)") (class "Default")
      (node (ref "Q7") (pin "2") (pinfunction "B_2") (pintype "passive"))
      (node (ref "Q9") (pin "3") (pinfunction "C_3") (pintype "passive"))
      (node (ref "R22") (pin "2") (pinfunction "2_2") (pintype "passive"))
      (node (ref "R23") (pin "1") (pinfunction "1_1") (pintype "passive"))
    )
    (net (code "37") (name "Net-(Q7-E)") (class "Default")
      (node (ref "Q7") (pin "1") (pinfunction "E_1") (pintype "passive"))
      (node (ref "R15") (pin "2") (pinfunction "2_2") (pintype "passive"))
    )
    (net (code "38") (name "Net-(Q8-C)") (class "Default")
      (node (ref "Q8") (pin "3") (pinfunction "C_3") (pintype "passive"))
      (node (ref "R18") (pin "2") (pinfunction "2_2") (pintype "passive"))
    )
    (net (code "39") (name "Net-(Q9-B)") (class "Default")
      (node (ref "C3") (pin "1") (pinfunction "1_1") (pintype "passive"))
      (node (ref "Q9") (pin "2") (pinfunction "B_2") (pintype "passive"))
      (node (ref "R19") (pin "1") (pinfunction "1_1") (pintype "passive"))
    )
    (net (code "40") (name "Net-(Q9-E)") (class "Default")
      (node (ref "Q9") (pin "1") (pinfunction "E_1") (pintype "passive"))
      (node (ref "R14") (pin "2") (pinfunction "2_2") (pintype "passive"))
      (node (ref "R15") (pin "1") (pinfunction "1_1") (pintype "passive"))
    )
    (net (code "41") (name "Net-(Q10-B)") (class "Default")
      (node (ref "Q10") (pin "2") (pinfunction "B_2") (pintype "passive"))
      (node (ref "R20") (pin "2") (pinfunction "2_2") (pintype "passive"))
      (node (ref "R21") (pin "1") (pinfunction "1_1") (pintype "passive"))
    )
    (net (code "42") (name "Net-(Q10-E)") (class "Default")
      (node (ref "Q10") (pin "1") (pinfunction "E_1") (pintype "passive"))
      (node (ref "Q11") (pin "1") (pinfunction "E_1") (pintype "passive"))
      (node (ref "R24") (pin "2") (pinfunction "2_2") (pintype "passive"))
      (node (ref "R25") (pin "1") (pinfunction "1_1") (pintype "passive"))
    )
    (net (code "43") (name "Net-(Q11-B)") (class "Default")
      (node (ref "C4") (pin "2") (pinfunction "2_2") (pintype "passive"))
      (node (ref "D4") (pin "C") (pinfunction "C_C") (pintype "passive"))
      (node (ref "Q11") (pin "2") (pinfunction "B_2") (pintype "passive"))
      (node (ref "R25") (pin "2") (pinfunction "2_2") (pintype "passive"))
    )
    (net (code "44") (name "Net-(Q12-B)") (class "Default")
      (node (ref "Q12") (pin "2") (pinfunction "B_2") (pintype "passive"))
      (node (ref "R28") (pin "2") (pinfunction "S_2") (pintype "passive"))
    )
    (net (code "45") (name "Net-(Q12-E)") (class "Default")
      (node (ref "Q12") (pin "1") (pinfunction "E_1") (pintype "passive"))
      (node (ref "Q13") (pin "1") (pinfunction "E_1") (pintype "passive"))
      (node (ref "R31") (pin "2") (pinfunction "2_2") (pintype "passive"))
    )
    (net (code "46") (name "Net-(Q13-B)") (class "Default")
      (node (ref "C5") (pin "+") (pinfunction "+_+") (pintype "passive"))
      (node (ref "C6") (pin "2") (pinfunction "2_2") (pintype "passive"))
      (node (ref "Q13") (pin "2") (pinfunction "B_2") (pintype "passive"))
      (node (ref "R32") (pin "1") (pinfunction "1_1") (pintype "passive"))
      (node (ref "R35") (pin "2") (pinfunction "2_2") (pintype "passive"))
      (node (ref "U$1") (pin "BR2") (pinfunction "1_BR2") (pintype "bidirectional"))
    )
    (net (code "47") (name "Net-(Q13-C)") (class "Default")
      (node (ref "C8") (pin "1") (pinfunction "1_1") (pintype "passive"))
      (node (ref "D7") (pin "A") (pinfunction "A_A") (pintype "passive"))
      (node (ref "Q13") (pin "3") (pinfunction "C_3") (pintype "passive"))
      (node (ref "Q15") (pin "2") (pinfunction "B_2") (pintype "passive"))
      (node (ref "R41") (pin "1") (pinfunction "1_1") (pintype "passive"))
    )
    (net (code "48") (name "Net-(Q14-B)") (class "Default")
      (node (ref "Q14") (pin "2") (pinfunction "B_2") (pintype "passive"))
      (node (ref "R37") (pin "2") (pinfunction "2_2") (pintype "passive"))
    )
    (net (code "49") (name "Net-(Q14-C)") (class "Default")
      (node (ref "C14") (pin "2") (pinfunction "2_2") (pintype "passive"))
      (node (ref "D7") (pin "C") (pinfunction "C_C") (pintype "passive"))
      (node (ref "Q14") (pin "3") (pinfunction "C_3") (pintype "passive"))
      (node (ref "R38") (pin "2") (pinfunction "2_2") (pintype "passive"))
      (node (ref "U$1") (pin "BF2") (pinfunction "1_BF2") (pintype "bidirectional"))
    )
    (net (code "50") (name "Net-(Q14-E)") (class "Default")
      (node (ref "D10") (pin "A") (pinfunction "A_A") (pintype "passive"))
      (node (ref "Q14") (pin "1") (pinfunction "E_1") (pintype "passive"))
      (node (ref "R39") (pin "1") (pinfunction "1_1") (pintype "passive"))
    )
    (net (code "51") (name "Net-(Q15-C)") (class "Default")
      (node (ref "Q15") (pin "3") (pinfunction "C_3") (pintype "passive"))
      (node (ref "Q16") (pin "B") (pinfunction "B_B") (pintype "passive"))
      (node (ref "R40") (pin "2") (pinfunction "2_2") (pintype "passive"))
      (node (ref "R42") (pin "2") (pinfunction "2_2") (pintype "passive"))
      (node (ref "R43") (pin "2") (pinfunction "2_2") (pintype "passive"))
      (node (ref "R44") (pin "2") (pinfunction "2_2") (pintype "passive"))
    )
    (net (code "52") (name "Net-(Q16-PadC)") (class "Default")
      (node (ref "Q16") (pin "C") (pinfunction "C_C") (pintype "passive"))
      (node (ref "Q16") (pin "C/") (pinfunction "C/_C/") (pintype "passive"))
      (node (ref "R45") (pin "2") (pinfunction "2_2") (pintype "passive"))
      (node (ref "R47") (pin "2") (pinfunction "2_2") (pintype "passive"))
      (node (ref "R48") (pin "2") (pinfunction "2_2") (pintype "passive"))
      (node (ref "R49") (pin "2") (pinfunction "2_2") (pintype "passive"))
    )
    (net (code "53") (name "Net-(Q17-B)") (class "Default")
      (node (ref "C7") (pin "-") (pinfunction "-_-") (pintype "passive"))
      (node (ref "Q17") (pin "2") (pinfunction "B_2") (pintype "passive"))
      (node (ref "R50") (pin "1") (pinfunction "1_1") (pintype "passive"))
    )
    (net (code "54") (name "Net-(R2-E)") (class "Default")
      (node (ref "R2") (pin "3") (pinfunction "E_3") (pintype "passive"))
      (node (ref "R3") (pin "1") (pinfunction "1_1") (pintype "passive"))
    )
    (net (code "55") (name "Net-(R28-A)") (class "Default")
      (node (ref "R27") (pin "2") (pinfunction "2_2") (pintype "passive"))
      (node (ref "R28") (pin "1") (pinfunction "A_1") (pintype "passive"))
    )
    (net (code "56") (name "Net-(R28-E)") (class "Default")
      (node (ref "R28") (pin "3") (pinfunction "E_3") (pintype "passive"))
      (node (ref "R29") (pin "1") (pinfunction "1_1") (pintype "passive"))
    )
    (net (code "57") (name "Net-(U$1AB-1)") (class "Default")
      (node (ref "R53") (pin "1") (pinfunction "1_1") (pintype "passive"))
      (node (ref "U$1") (pin "AR2") (pinfunction "1_AR2") (pintype "bidirectional"))
    )
    (net (code "58") (name "Net-(U$1AZ-1)") (class "Default")
      (node (ref "D12") (pin "A") (pinfunction "A_A") (pintype "passive"))
      (node (ref "R46") (pin "1") (pinfunction "1_1") (pintype "passive"))
      (node (ref "U$1") (pin "BJ2") (pinfunction "1_BJ2") (pintype "bidirectional"))
      (node (ref "U$1") (pin "BK2") (pinfunction "1_BK2") (pintype "bidirectional"))
    )
    (net (code "59") (name "Net-(U$1BN-1)") (class "Default")
      (node (ref "C5") (pin "-") (pinfunction "-_-") (pintype "passive"))
      (node (ref "D6") (pin "A") (pinfunction "A_A") (pintype "passive"))
      (node (ref "R34") (pin "2") (pinfunction "2_2") (pintype "passive"))
      (node (ref "R35") (pin "1") (pinfunction "1_1") (pintype "passive"))
      (node (ref "U$1") (pin "BS2") (pinfunction "1_BS2") (pintype "bidirectional"))
    )
    (net (code "60") (name "VCC") (class "Default")
      (node (ref "C10") (pin "+") (pinfunction "+_+") (pintype "passive"))
      (node (ref "C11") (pin "1") (pinfunction "1_1") (pintype "passive"))
      (node (ref "C12") (pin "1") (pinfunction "1_1") (pintype "passive"))
      (node (ref "C13") (pin "1") (pinfunction "1_1") (pintype "passive"))
      (node (ref "C9") (pin "+") (pinfunction "+_+") (pintype "passive"))
      (node (ref "Q6") (pin "1") (pinfunction "E_1") (pintype "passive"))
      (node (ref "Q8") (pin "1") (pinfunction "E_1") (pintype "passive"))
      (node (ref "R11") (pin "2") (pinfunction "2_2") (pintype "passive"))
      (node (ref "R16") (pin "2") (pinfunction "2_2") (pintype "passive"))
      (node (ref "R23") (pin "2") (pinfunction "2_2") (pintype "passive"))
      (node (ref "R26") (pin "2") (pinfunction "2_2") (pintype "passive"))
      (node (ref "R3") (pin "2") (pinfunction "2_2") (pintype "passive"))
      (node (ref "R33") (pin "2") (pinfunction "2_2") (pintype "passive"))
      (node (ref "R39") (pin "2") (pinfunction "2_2") (pintype "passive"))
      (node (ref "R4") (pin "2") (pinfunction "2_2") (pintype "passive"))
      (node (ref "R50") (pin "2") (pinfunction "2_2") (pintype "passive"))
      (node (ref "R51") (pin "2") (pinfunction "2_2") (pintype "passive"))
      (node (ref "R53") (pin "2") (pinfunction "2_2") (pintype "passive"))
      (node (ref "R54") (pin "2") (pinfunction "2_2") (pintype "passive"))
      (node (ref "R55") (pin "2") (pinfunction "2_2") (pintype "passive"))
      (node (ref "R7") (pin "2") (pinfunction "2_2") (pintype "passive"))
      (node (ref "U$1") (pin "AA2") (pinfunction "1_AA2") (pintype "bidirectional"))
      (node (ref "U$1") (pin "BA2") (pinfunction "1_BA2") (pintype "bidirectional"))
    )
  )
)
